# Sheet1.net
KiCad netlist of a schematic drawn in Altium Designer
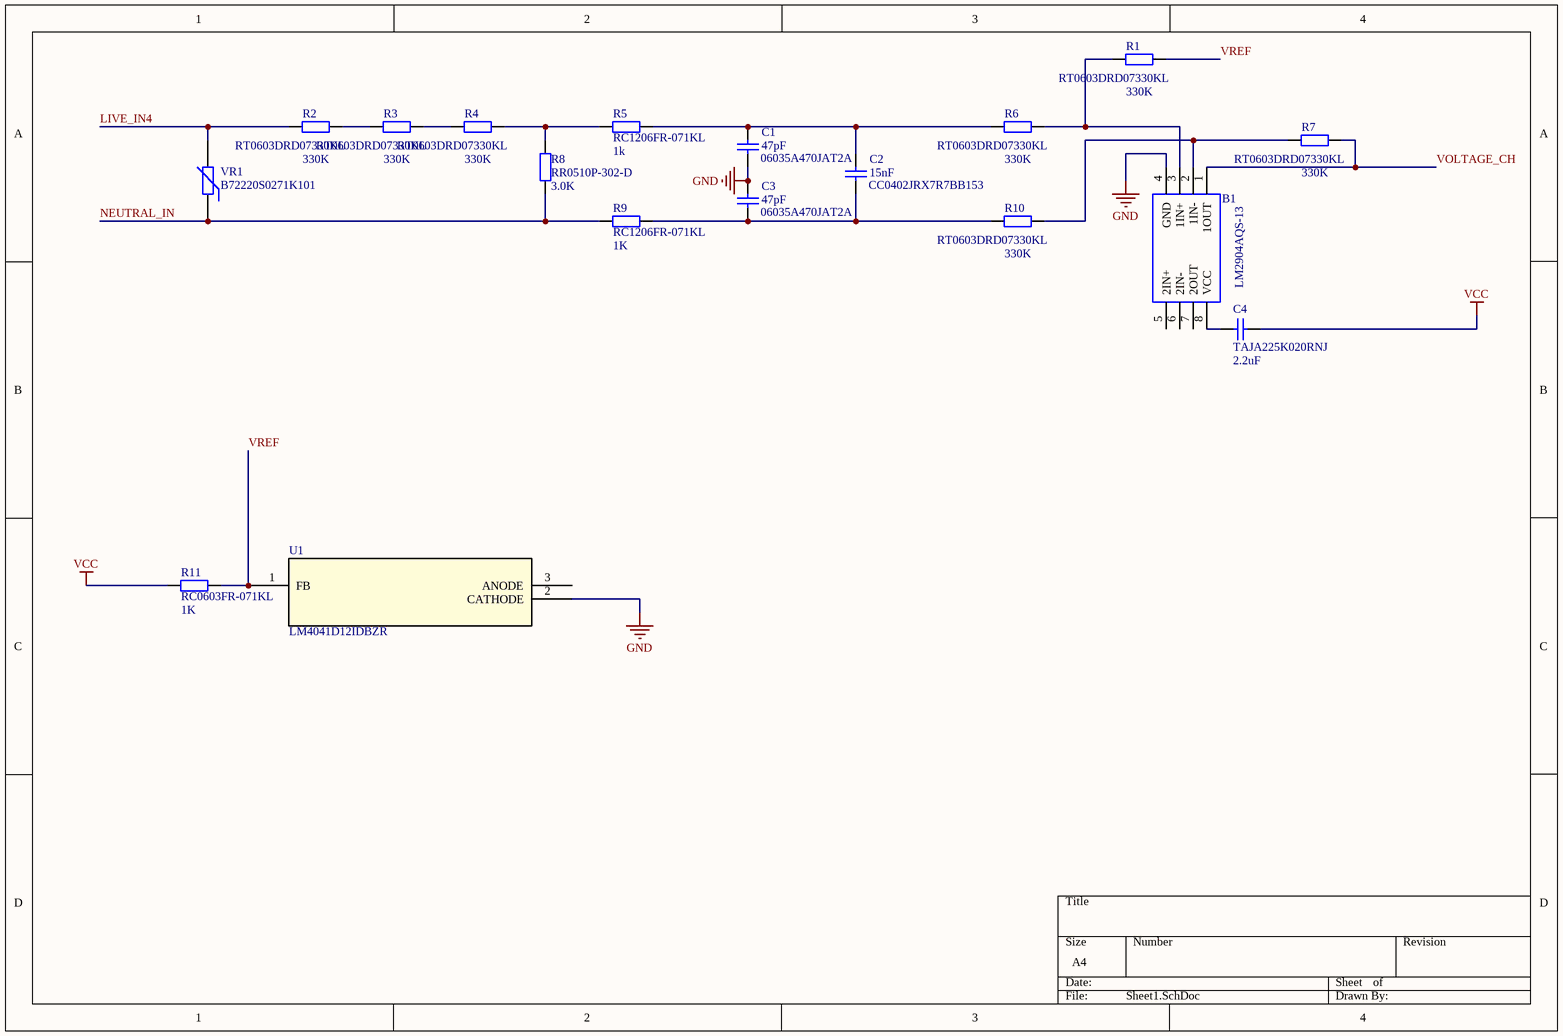
[diagram p0: Sheet1.SchDoc]

(export (version "E")
  (design (tool "Eeschema 10.0.6"))
  (components
    (comp (ref "B1")
      (value "LM2904AQS-13")
      (footprint "SOIC127P600X175-8N:SOIC127P600X175-8N")
      (description "https://www.diodes.com/assets/Datasheets/LM2902_04.pdf")
      (fields (field (name "MANUFACTURER_PART_NUMBER") "LM2904AS-13"))
      (libsource (lib "LM2904AS-13") (part "LM2904AS-13"))
    )
    (comp (ref "C1")
      (value "06035A470JAT2A")
      (footprint "AltiumDesigner:0603-M")
      (description "Capacitor")
      (fields (field (name "ALTIUM_VALUE") "47pF") (field (name "PUBLISHER") "Altium Limited"))
      (libsource (lib "Miscellaneous Devices") (part "Cap"))
    )
    (comp (ref "C2")
      (value "CC0402JRX7R7BB153")
      (footprint "CAPC1005X55N:CAPC1005X55N")
      (description "Capacitor")
      (fields (field (name "ALTIUM_VALUE") "15nF") (field (name "PUBLISHER") "Altium Limited"))
      (libsource (lib "Miscellaneous Devices") (part "Cap"))
    )
    (comp (ref "C3")
      (value "06035A470JAT2A")
      (footprint "AltiumDesigner:0603-M")
      (description "Capacitor")
      (fields (field (name "ALTIUM_VALUE") "47pF") (field (name "PUBLISHER") "Altium Limited"))
      (libsource (lib "Miscellaneous Devices") (part "Cap"))
    )
    (comp (ref "C4")
      (value "TAJA225K020RNJ")
      (footprint "CAPPM3216X180N:CAPPM3216X180N")
      (description "Capacitor")
      (fields (field (name "ALTIUM_VALUE") "2.2uF") (field (name "PUBLISHER") "Altium Limited"))
      (libsource (lib "Miscellaneous Devices") (part "Cap"))
    )
    (comp (ref "R1")
      (value "RT0603DRD07330KL")
      (footprint "AltiumDesigner:RC0603N-M")
      (description "Resistor")
      (fields (field (name "ALTIUM_VALUE") "330K") (field (name "PUBLISHER") "Altium Limited"))
      (libsource (lib "Miscellaneous Devices") (part "Res2"))
    )
    (comp (ref "R2")
      (value "RT0603DRD07330KL")
      (footprint "AltiumDesigner:RC0603N-M")
      (description "Resistor")
      (fields (field (name "ALTIUM_VALUE") "330K") (field (name "PUBLISHER") "Altium Limited"))
      (libsource (lib "Miscellaneous Devices") (part "Res2"))
    )
    (comp (ref "R3")
      (value "RT0603DRD07330KL")
      (footprint "AltiumDesigner:RC0603N-M")
      (description "Resistor")
      (fields (field (name "ALTIUM_VALUE") "330K") (field (name "PUBLISHER") "Altium Limited"))
      (libsource (lib "Miscellaneous Devices") (part "Res2"))
    )
    (comp (ref "R4")
      (value "RT0603DRD07330KL")
      (footprint "AltiumDesigner:RC0603N-M")
      (description "Resistor")
      (fields (field (name "ALTIUM_VALUE") "330K") (field (name "PUBLISHER") "Altium Limited"))
      (libsource (lib "Miscellaneous Devices") (part "Res2"))
    )
    (comp (ref "R5")
      (value "RC1206FR-071KL")
      (footprint "AltiumDesigner:RC1206N-M")
      (description "Resistor")
      (fields (field (name "ALTIUM_VALUE") "1k") (field (name "PUBLISHER") "Altium Limited"))
      (libsource (lib "") (part "Res2_1"))
    )
    (comp (ref "R6")
      (value "RT0603DRD07330KL")
      (footprint "AltiumDesigner:RC0603N-M")
      (description "Resistor")
      (fields (field (name "ALTIUM_VALUE") "330K") (field (name "PUBLISHER") "Altium Limited"))
      (libsource (lib "Miscellaneous Devices") (part "Res2"))
    )
    (comp (ref "R7")
      (value "RT0603DRD07330KL")
      (footprint "AltiumDesigner:RC0603N-M")
      (description "Resistor")
      (fields (field (name "ALTIUM_VALUE") "330K") (field (name "PUBLISHER") "Altium Limited"))
      (libsource (lib "Miscellaneous Devices") (part "Res2"))
    )
    (comp (ref "R8")
      (value "RR0510P-302-D")
      (footprint "AltiumDesigner:RES_0510-M")
      (description "Resistor")
      (fields (field (name "ALTIUM_VALUE") "3.0K") (field (name "PUBLISHER") "Altium Limited"))
      (libsource (lib "") (part "Res2_2"))
    )
    (comp (ref "R9")
      (value "RC1206FR-071KL")
      (footprint "AltiumDesigner:RC1206N-M")
      (description "Resistor")
      (fields (field (name "ALTIUM_VALUE") "1K") (field (name "PUBLISHER") "Altium Limited"))
      (libsource (lib "") (part "Res2_1"))
    )
    (comp (ref "R10")
      (value "RT0603DRD07330KL")
      (footprint "AltiumDesigner:RC0603N-M")
      (description "Resistor")
      (fields (field (name "ALTIUM_VALUE") "330K") (field (name "PUBLISHER") "Altium Limited"))
      (libsource (lib "Miscellaneous Devices") (part "Res2"))
    )
    (comp (ref "R11")
      (value "RC0603FR-071KL")
      (footprint "AltiumDesigner:RC0603N-M")
      (description "Resistor")
      (fields (field (name "ALTIUM_VALUE") "1K") (field (name "PUBLISHER") "Altium Limited"))
      (libsource (lib "Miscellaneous Devices") (part "Res2"))
    )
    (comp (ref "U1")
      (value "LM4041D12IDBZR")
      (footprint "AltiumDesigner:DBZ3-M")
      (description "Imported")
      (fields (field (name "MANUFACTURER") "Texas Instruments"))
      (libsource (lib "AltiumDesigner") (part "LM4041D12IDBZR"))
    )
    (comp (ref "VR1")
      (value "B72220S0271K101")
      (footprint "B722_21.5X5.4_:B722(21.5X5.4)")
      (description "Varistor (Voltage-Sensitive Resistor)")
      (fields (field (name "PUBLISHER") "Altium Limited"))
      (libsource (lib "Miscellaneous Devices") (part "Res Varistor"))
    )
  )
  (nets
    (net (code "1") (name "/LIVE_IN4") (class "Default")
      (node (ref "R2") (pin "1") (pinfunction "1_1") (pintype "passive"))
      (node (ref "VR1") (pin "2") (pinfunction "2_2") (pintype "passive"))
    )
    (net (code "2") (name "/NEUTRAL_IN") (class "Default")
      (node (ref "R8") (pin "1") (pinfunction "1_1") (pintype "passive"))
      (node (ref "R9") (pin "2") (pinfunction "2_2") (pintype "passive"))
      (node (ref "VR1") (pin "1") (pinfunction "1_1") (pintype "passive"))
    )
    (net (code "3") (name "/VOLTAGE_CH") (class "Default")
      (node (ref "B1") (pin "1") (pinfunction "1OUT_1") (pintype "passive"))
      (node (ref "R7") (pin "2") (pinfunction "2_2") (pintype "passive"))
    )
    (net (code "4") (name "/VREF") (class "Default")
      (node (ref "R1") (pin "2") (pinfunction "2_2") (pintype "passive"))
      (node (ref "R11") (pin "2") (pinfunction "2_2") (pintype "passive"))
      (node (ref "U1") (pin "1") (pinfunction "FB_1") (pintype "passive"))
    )
    (net (code "5") (name "GND") (class "Default")
      (node (ref "B1") (pin "4") (pinfunction "GND_4") (pintype "passive"))
      (node (ref "C1") (pin "1") (pinfunction "1_1") (pintype "passive"))
      (node (ref "C3") (pin "2") (pinfunction "2_2") (pintype "passive"))
      (node (ref "U1") (pin "2") (pinfunction "CATHODE_2") (pintype "passive"))
    )
    (net (code "6") (name "Net-(B1-1IN+)") (class "Default")
      (node (ref "B1") (pin "3") (pinfunction "1IN+_3") (pintype "passive"))
      (node (ref "R1") (pin "1") (pinfunction "1_1") (pintype "passive"))
      (node (ref "R6") (pin "2") (pinfunction "2_2") (pintype "passive"))
    )
    (net (code "7") (name "Net-(B1-1IN-)") (class "Default")
      (node (ref "B1") (pin "2") (pinfunction "1IN-_2") (pintype "passive"))
      (node (ref "R10") (pin "2") (pinfunction "2_2") (pintype "passive"))
      (node (ref "R7") (pin "1") (pinfunction "1_1") (pintype "passive"))
    )
    (net (code "8") (name "Net-(B1-VCC)") (class "Default")
      (node (ref "B1") (pin "8") (pinfunction "VCC_8") (pintype "power_in"))
      (node (ref "C4") (pin "2") (pinfunction "2_2") (pintype "passive"))
    )
    (net (code "9") (name "Net-(C1-Pad2)") (class "Default")
      (node (ref "C1") (pin "2") (pinfunction "2_2") (pintype "passive"))
      (node (ref "C2") (pin "2") (pinfunction "2_2") (pintype "passive"))
      (node (ref "R5") (pin "1") (pinfunction "1_1") (pintype "passive"))
      (node (ref "R6") (pin "1") (pinfunction "1_1") (pintype "passive"))
    )
    (net (code "10") (name "Net-(C2-Pad1)") (class "Default")
      (node (ref "C2") (pin "1") (pinfunction "1_1") (pintype "passive"))
      (node (ref "C3") (pin "1") (pinfunction "1_1") (pintype "passive"))
      (node (ref "R10") (pin "1") (pinfunction "1_1") (pintype "passive"))
      (node (ref "R9") (pin "1") (pinfunction "1_1") (pintype "passive"))
    )
    (net (code "11") (name "Net-(R2-Pad2)") (class "Default")
      (node (ref "R2") (pin "2") (pinfunction "2_2") (pintype "passive"))
      (node (ref "R3") (pin "1") (pinfunction "1_1") (pintype "passive"))
    )
    (net (code "12") (name "Net-(R3-Pad2)") (class "Default")
      (node (ref "R3") (pin "2") (pinfunction "2_2") (pintype "passive"))
      (node (ref "R4") (pin "1") (pinfunction "1_1") (pintype "passive"))
    )
    (net (code "13") (name "Net-(R4-Pad2)") (class "Default")
      (node (ref "R4") (pin "2") (pinfunction "2_2") (pintype "passive"))
      (node (ref "R5") (pin "2") (pinfunction "2_2") (pintype "passive"))
      (node (ref "R8") (pin "2") (pinfunction "2_2") (pintype "passive"))
    )
    (net (code "14") (name "VCC") (class "Default")
      (node (ref "C4") (pin "1") (pinfunction "1_1") (pintype "passive"))
      (node (ref "R11") (pin "1") (pinfunction "1_1") (pintype "passive"))
    )
    (net (code "15") (name "unconnected-(B1-2IN+-Pad5)") (class "Default")
      (node (ref "B1") (pin "5") (pinfunction "2IN+_5") (pintype "passive"))
    )
    (net (code "16") (name "unconnected-(B1-2IN--Pad6)") (class "Default")
      (node (ref "B1") (pin "6") (pinfunction "2IN-_6") (pintype "passive"))
    )
    (net (code "17") (name "unconnected-(B1-2OUT-Pad7)") (class "Default")
      (node (ref "B1") (pin "7") (pinfunction "2OUT_7") (pintype "passive"))
    )
    (net (code "18") (name "unconnected-(U1-ANODE-Pad3)") (class "Default")
      (node (ref "U1") (pin "3") (pinfunction "ANODE_3") (pintype "passive"))
    )
  )
)
